# pcbremote.net
KiCad netlist of a schematic drawn in EAGLE
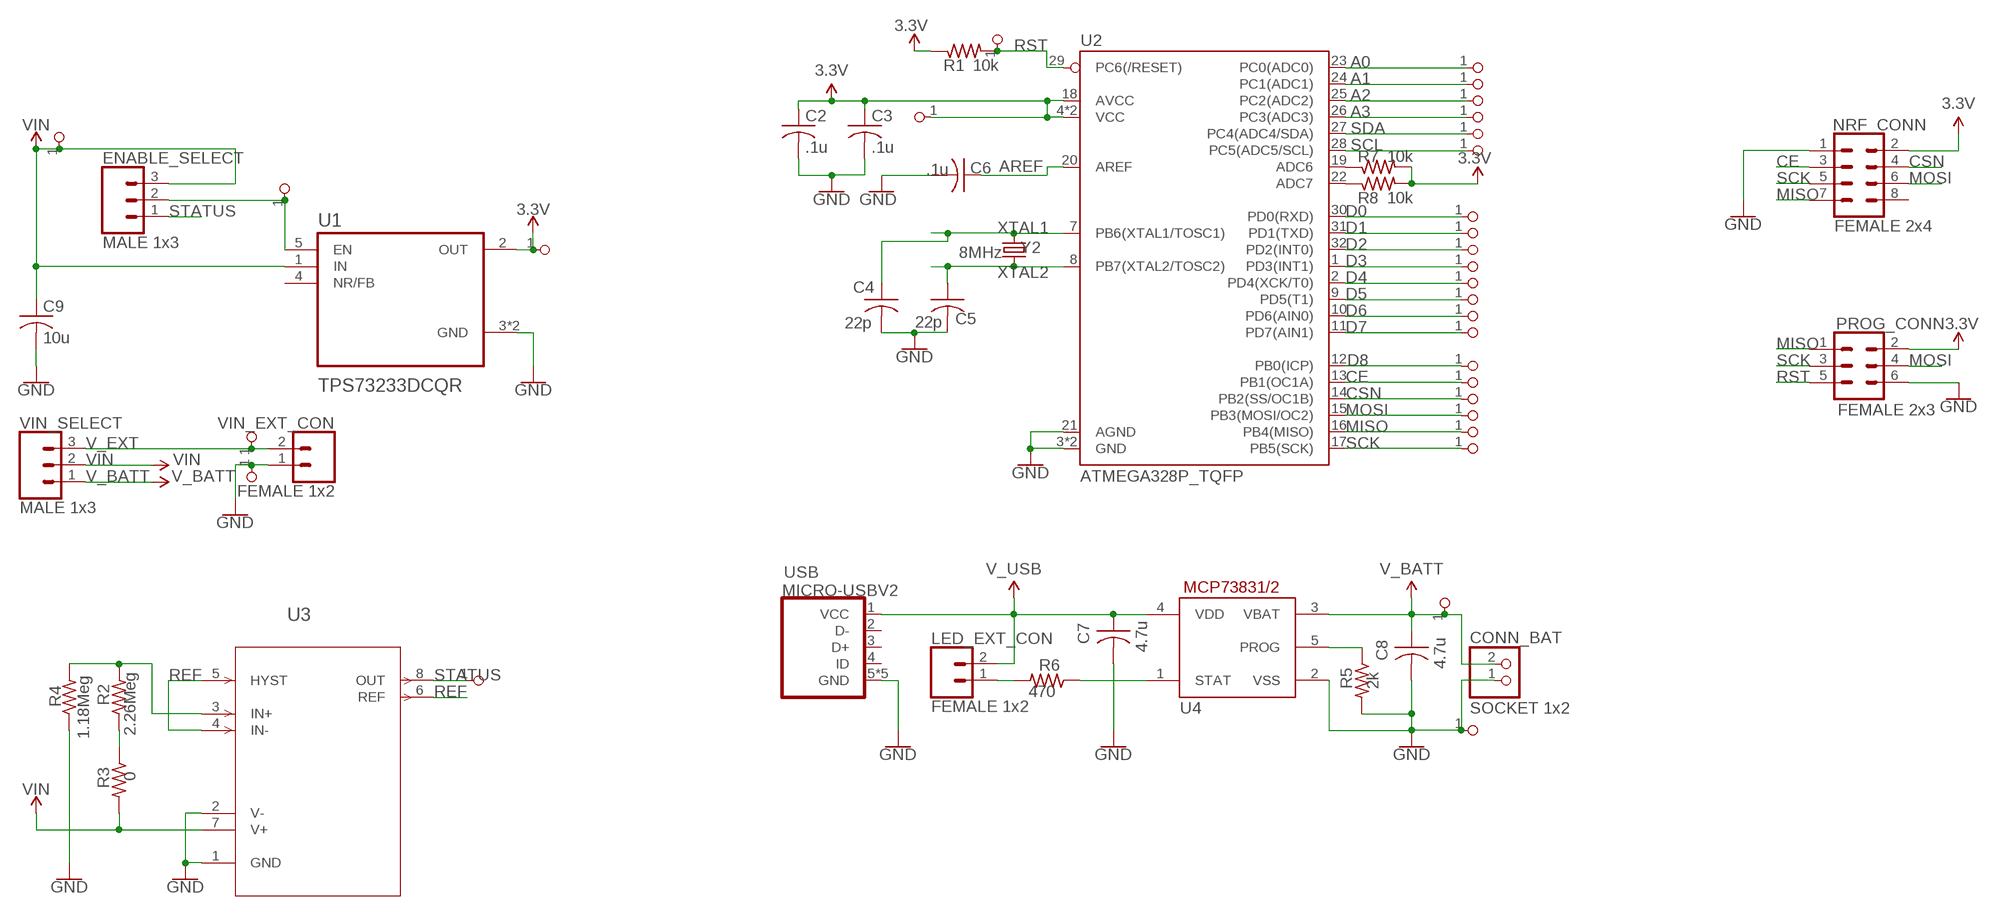
[diagram p0: schematic, sheet 1]

(export (version "E")
  (design (tool "Eeschema 10.0.6"))
  (components
    (comp (ref "3.3V")
      (value "PINHD-1X1")
      (footprint "eagle-import:1X01")
      (libsource (lib "eagle-import") (part "PINHD-1X1"))
    )
    (comp (ref "A0")
      (value "PINHD-1X1")
      (footprint "eagle-import:1X01")
      (libsource (lib "eagle-import") (part "PINHD-1X1"))
    )
    (comp (ref "A1")
      (value "PINHD-1X1")
      (footprint "eagle-import:1X01")
      (libsource (lib "eagle-import") (part "PINHD-1X1"))
    )
    (comp (ref "A2")
      (value "PINHD-1X1")
      (footprint "eagle-import:1X01")
      (libsource (lib "eagle-import") (part "PINHD-1X1"))
    )
    (comp (ref "A3")
      (value "PINHD-1X1")
      (footprint "eagle-import:1X01")
      (libsource (lib "eagle-import") (part "PINHD-1X1"))
    )
    (comp (ref "C2")
      (value ".1u")
      (footprint "eagle-import:C0805")
      (libsource (lib "eagle-import") (part "C-USC0805"))
    )
    (comp (ref "C3")
      (value ".1u")
      (footprint "eagle-import:C0805")
      (libsource (lib "eagle-import") (part "C-USC0805"))
    )
    (comp (ref "C4")
      (value "22p")
      (footprint "eagle-import:C0805")
      (libsource (lib "eagle-import") (part "C-USC0805"))
    )
    (comp (ref "C5")
      (value "22p")
      (footprint "eagle-import:C0805")
      (libsource (lib "eagle-import") (part "C-USC0805"))
    )
    (comp (ref "C6")
      (value ".1u")
      (footprint "eagle-import:C0805")
      (libsource (lib "eagle-import") (part "C-USC0805"))
    )
    (comp (ref "C7")
      (value "4.7u")
      (footprint "eagle-import:C0805")
      (libsource (lib "eagle-import") (part "C-USC0805"))
    )
    (comp (ref "C8")
      (value "4.7u")
      (footprint "eagle-import:C0805")
      (libsource (lib "eagle-import") (part "C-USC0805"))
    )
    (comp (ref "C9")
      (value "10u")
      (footprint "eagle-import:C0805")
      (libsource (lib "eagle-import") (part "C-USC0805"))
    )
    (comp (ref "CE")
      (value "PINHD-1X1")
      (footprint "eagle-import:1X01")
      (libsource (lib "eagle-import") (part "PINHD-1X1"))
    )
    (comp (ref "CONN_BAT")
      (value "SOCKET 1x2")
      (footprint "eagle-import:JST-PH-2-THM")
      (libsource (lib "eagle-import") (part "JST_2PIN-THM"))
    )
    (comp (ref "CSN")
      (value "PINHD-1X1")
      (footprint "eagle-import:1X01")
      (libsource (lib "eagle-import") (part "PINHD-1X1"))
    )
    (comp (ref "D0")
      (value "PINHD-1X1")
      (footprint "eagle-import:1X01")
      (libsource (lib "eagle-import") (part "PINHD-1X1"))
    )
    (comp (ref "D1")
      (value "PINHD-1X1")
      (footprint "eagle-import:1X01")
      (libsource (lib "eagle-import") (part "PINHD-1X1"))
    )
    (comp (ref "D2")
      (value "PINHD-1X1")
      (footprint "eagle-import:1X01")
      (libsource (lib "eagle-import") (part "PINHD-1X1"))
    )
    (comp (ref "D3")
      (value "PINHD-1X1")
      (footprint "eagle-import:1X01")
      (libsource (lib "eagle-import") (part "PINHD-1X1"))
    )
    (comp (ref "D4")
      (value "PINHD-1X1")
      (footprint "eagle-import:1X01")
      (libsource (lib "eagle-import") (part "PINHD-1X1"))
    )
    (comp (ref "D5")
      (value "PINHD-1X1")
      (footprint "eagle-import:1X01")
      (libsource (lib "eagle-import") (part "PINHD-1X1"))
    )
    (comp (ref "D6")
      (value "PINHD-1X1")
      (footprint "eagle-import:1X01")
      (libsource (lib "eagle-import") (part "PINHD-1X1"))
    )
    (comp (ref "D7")
      (value "PINHD-1X1")
      (footprint "eagle-import:1X01")
      (libsource (lib "eagle-import") (part "PINHD-1X1"))
    )
    (comp (ref "D8")
      (value "PINHD-1X1")
      (footprint "eagle-import:1X01")
      (libsource (lib "eagle-import") (part "PINHD-1X1"))
    )
    (comp (ref "EN")
      (value "PINHD-1X1")
      (footprint "eagle-import:1X01")
      (libsource (lib "eagle-import") (part "PINHD-1X1"))
    )
    (comp (ref "ENABLE_SELECT")
      (value "MALE 1x3")
      (footprint "eagle-import:1X03")
      (libsource (lib "eagle-import") (part "CONN_03"))
    )
    (comp (ref "GND")
      (value "PINHD-1X1")
      (footprint "eagle-import:1X01")
      (libsource (lib "eagle-import") (part "PINHD-1X1"))
    )
    (comp (ref "GND7")
      (value "PINHD-1X1")
      (footprint "eagle-import:1X01")
      (libsource (lib "eagle-import") (part "PINHD-1X1"))
    )
    (comp (ref "LED_EXT_CON")
      (value "FEMALE 1x2")
      (footprint "eagle-import:1X02")
      (libsource (lib "eagle-import") (part "CONN_02"))
    )
    (comp (ref "MISO")
      (value "PINHD-1X1")
      (footprint "eagle-import:1X01")
      (libsource (lib "eagle-import") (part "PINHD-1X1"))
    )
    (comp (ref "MOSI")
      (value "PINHD-1X1")
      (footprint "eagle-import:1X01")
      (libsource (lib "eagle-import") (part "PINHD-1X1"))
    )
    (comp (ref "NRF_CONN")
      (value "FEMALE 2x4")
      (footprint "eagle-import:2X4")
      (libsource (lib "eagle-import") (part "CONN_04X2"))
    )
    (comp (ref "PROG_CONN")
      (value "FEMALE 2x3")
      (footprint "eagle-import:2X3")
      (libsource (lib "eagle-import") (part "CONN_03X2FEMALE"))
    )
    (comp (ref "R1")
      (value "10k")
      (footprint "eagle-import:R0805")
      (libsource (lib "eagle-import") (part "R-US_R0805"))
    )
    (comp (ref "R2")
      (value "2.26Meg")
      (footprint "eagle-import:R0805")
      (libsource (lib "eagle-import") (part "R-US_R0805"))
    )
    (comp (ref "R3")
      (value "0")
      (footprint "eagle-import:R0805")
      (libsource (lib "eagle-import") (part "R-US_R0805"))
    )
    (comp (ref "R4")
      (value "1.18Meg")
      (footprint "eagle-import:R0805")
      (libsource (lib "eagle-import") (part "R-US_R0805"))
    )
    (comp (ref "R5")
      (value "2k")
      (footprint "eagle-import:R0805")
      (libsource (lib "eagle-import") (part "R-US_R0805"))
    )
    (comp (ref "R6")
      (value "470")
      (footprint "eagle-import:R0805")
      (libsource (lib "eagle-import") (part "R-US_R0805"))
    )
    (comp (ref "R7")
      (value "10k")
      (footprint "eagle-import:R0805")
      (libsource (lib "eagle-import") (part "R-US_R0805"))
    )
    (comp (ref "R8")
      (value "10k")
      (footprint "eagle-import:R0805")
      (libsource (lib "eagle-import") (part "R-US_R0805"))
    )
    (comp (ref "RESET")
      (value "PINHD-1X1")
      (footprint "eagle-import:1X01")
      (libsource (lib "eagle-import") (part "PINHD-1X1"))
    )
    (comp (ref "SCK")
      (value "PINHD-1X1")
      (footprint "eagle-import:1X01")
      (libsource (lib "eagle-import") (part "PINHD-1X1"))
    )
    (comp (ref "SCL")
      (value "PINHD-1X1")
      (footprint "eagle-import:1X01")
      (libsource (lib "eagle-import") (part "PINHD-1X1"))
    )
    (comp (ref "SDA")
      (value "PINHD-1X1")
      (footprint "eagle-import:1X01")
      (libsource (lib "eagle-import") (part "PINHD-1X1"))
    )
    (comp (ref "STATUS")
      (value "PINHD-1X1")
      (footprint "eagle-import:1X01")
      (libsource (lib "eagle-import") (part "PINHD-1X1"))
    )
    (comp (ref "U1")
      (value "TPS73233DCQR")
      (footprint "eagle-import:SOT127P706X180-6N")
      (fields (field (name "DIGI-KEY_PART_NUMBER") "296-16866-1-ND") (field (name "MF") "Texas Instruments"))
      (libsource (lib "eagle-import") (part "TPS73233DCQR"))
    )
    (comp (ref "U2")
      (value "ATMEGA328P_TQFP")
      (footprint "eagle-import:TQFP32-08")
      (libsource (lib "eagle-import") (part "ATMEGA328P_TQFP"))
    )
    (comp (ref "U3")
      (value "LTC1540CS8PBF")
      (footprint "eagle-import:SO-8_S_LIT")
      (fields (field (name "MANUFACTURER_PART_NUMBER") "ltc1540cs8#pbf"))
      (libsource (lib "eagle-import") (part "LTC1540CS8PBF"))
    )
    (comp (ref "U4")
      (value "MCP73831/OT")
      (footprint "eagle-import:SOT23-5L")
      (libsource (lib "eagle-import") (part "MCP73831/OT"))
    )
    (comp (ref "USB")
      (value "MICRO-USBV2")
      (footprint "eagle-import:MICRO-USB-2")
      (libsource (lib "eagle-import") (part "MICRO-USBV2"))
    )
    (comp (ref "VCC")
      (value "PINHD-1X1")
      (footprint "eagle-import:1X01")
      (libsource (lib "eagle-import") (part "PINHD-1X1"))
    )
    (comp (ref "VIN")
      (value "PINHD-1X1")
      (footprint "eagle-import:1X01")
      (libsource (lib "eagle-import") (part "PINHD-1X1"))
    )
    (comp (ref "VIN_EXT")
      (value "PINHD-1X1")
      (footprint "eagle-import:1X01")
      (libsource (lib "eagle-import") (part "PINHD-1X1"))
    )
    (comp (ref "VIN_EXT_CON")
      (value "FEMALE 1x2")
      (footprint "eagle-import:1X02")
      (libsource (lib "eagle-import") (part "CONN_02"))
    )
    (comp (ref "VIN_SELECT")
      (value "MALE 1x3")
      (footprint "eagle-import:1X03")
      (libsource (lib "eagle-import") (part "CONN_03"))
    )
    (comp (ref "V_BATT")
      (value "PINHD-1X1")
      (footprint "eagle-import:1X01")
      (libsource (lib "eagle-import") (part "PINHD-1X1"))
    )
    (comp (ref "Y2")
      (value "8MHz")
      (footprint "eagle-import:CRYSTAL-SMD-5X3.2-4PAD")
      (libsource (lib "eagle-import") (part "CRYSTAL-8MHZSMD-5X3.2"))
    )
  )
  (nets
    (net (code "1") (name "/A0") (class "Default")
      (node (ref "A0") (pin "1") (pinfunction "1_1") (pintype "passive"))
      (node (ref "U2") (pin "23") (pinfunction "PC0(ADC0)_23") (pintype "bidirectional"))
    )
    (net (code "2") (name "/A1") (class "Default")
      (node (ref "A1") (pin "1") (pinfunction "1_1") (pintype "passive"))
      (node (ref "U2") (pin "24") (pinfunction "PC1(ADC1)_24") (pintype "bidirectional"))
    )
    (net (code "3") (name "/A2") (class "Default")
      (node (ref "A2") (pin "1") (pinfunction "1_1") (pintype "passive"))
      (node (ref "U2") (pin "25") (pinfunction "PC2(ADC2)_25") (pintype "bidirectional"))
    )
    (net (code "4") (name "/A3") (class "Default")
      (node (ref "A3") (pin "1") (pinfunction "1_1") (pintype "passive"))
      (node (ref "U2") (pin "26") (pinfunction "PC3(ADC3)_26") (pintype "bidirectional"))
    )
    (net (code "5") (name "/AREF") (class "Default")
      (node (ref "C6") (pin "1") (pinfunction "1_1") (pintype "passive"))
      (node (ref "U2") (pin "20") (pinfunction "AREF_20") (pintype "bidirectional"))
    )
    (net (code "6") (name "/CE") (class "Default")
      (node (ref "CE") (pin "1") (pinfunction "1_1") (pintype "passive"))
      (node (ref "NRF_CONN") (pin "3") (pinfunction "3_3") (pintype "passive"))
      (node (ref "U2") (pin "13") (pinfunction "PB1(OC1A)_13") (pintype "bidirectional"))
    )
    (net (code "7") (name "/CSN") (class "Default")
      (node (ref "CSN") (pin "1") (pinfunction "1_1") (pintype "passive"))
      (node (ref "NRF_CONN") (pin "4") (pinfunction "4_4") (pintype "passive"))
      (node (ref "U2") (pin "14") (pinfunction "PB2(SS/OC1B)_14") (pintype "bidirectional"))
    )
    (net (code "8") (name "/D0") (class "Default")
      (node (ref "D0") (pin "1") (pinfunction "1_1") (pintype "passive"))
      (node (ref "U2") (pin "30") (pinfunction "PD0(RXD)_30") (pintype "bidirectional"))
    )
    (net (code "9") (name "/D1") (class "Default")
      (node (ref "D1") (pin "1") (pinfunction "1_1") (pintype "passive"))
      (node (ref "U2") (pin "31") (pinfunction "PD1(TXD)_31") (pintype "bidirectional"))
    )
    (net (code "10") (name "/D2") (class "Default")
      (node (ref "D2") (pin "1") (pinfunction "1_1") (pintype "passive"))
      (node (ref "U2") (pin "32") (pinfunction "PD2(INT0)_32") (pintype "bidirectional"))
    )
    (net (code "11") (name "/D3") (class "Default")
      (node (ref "D3") (pin "1") (pinfunction "1_1") (pintype "passive"))
      (node (ref "U2") (pin "1") (pinfunction "PD3(INT1)_1") (pintype "bidirectional"))
    )
    (net (code "12") (name "/D4") (class "Default")
      (node (ref "D4") (pin "1") (pinfunction "1_1") (pintype "passive"))
      (node (ref "U2") (pin "2") (pinfunction "PD4(XCK/T0)_2") (pintype "bidirectional"))
    )
    (net (code "13") (name "/D5") (class "Default")
      (node (ref "D5") (pin "1") (pinfunction "1_1") (pintype "passive"))
      (node (ref "U2") (pin "9") (pinfunction "PD5(T1)_9") (pintype "bidirectional"))
    )
    (net (code "14") (name "/D6") (class "Default")
      (node (ref "D6") (pin "1") (pinfunction "1_1") (pintype "passive"))
      (node (ref "U2") (pin "10") (pinfunction "PD6(AIN0)_10") (pintype "bidirectional"))
    )
    (net (code "15") (name "/D7") (class "Default")
      (node (ref "D7") (pin "1") (pinfunction "1_1") (pintype "passive"))
      (node (ref "U2") (pin "11") (pinfunction "PD7(AIN1)_11") (pintype "bidirectional"))
    )
    (net (code "16") (name "/D8") (class "Default")
      (node (ref "D8") (pin "1") (pinfunction "1_1") (pintype "passive"))
      (node (ref "U2") (pin "12") (pinfunction "PB0(ICP)_12") (pintype "bidirectional"))
    )
    (net (code "17") (name "/MISO") (class "Default")
      (node (ref "MISO") (pin "1") (pinfunction "1_1") (pintype "passive"))
      (node (ref "NRF_CONN") (pin "7") (pinfunction "7_7") (pintype "passive"))
      (node (ref "PROG_CONN") (pin "1") (pinfunction "1_1") (pintype "bidirectional"))
      (node (ref "U2") (pin "16") (pinfunction "PB4(MISO)_16") (pintype "bidirectional"))
    )
    (net (code "18") (name "/MOSI") (class "Default")
      (node (ref "MOSI") (pin "1") (pinfunction "1_1") (pintype "passive"))
      (node (ref "NRF_CONN") (pin "6") (pinfunction "6_6") (pintype "passive"))
      (node (ref "PROG_CONN") (pin "4") (pinfunction "4_4") (pintype "bidirectional"))
      (node (ref "U2") (pin "15") (pinfunction "PB3(MOSI/OC2)_15") (pintype "bidirectional"))
    )
    (net (code "19") (name "/REF") (class "Default")
      (node (ref "U3") (pin "4") (pinfunction "IN-_4") (pintype "input"))
      (node (ref "U3") (pin "5") (pinfunction "HYST_5") (pintype "input"))
      (node (ref "U3") (pin "6") (pinfunction "REF_6") (pintype "output"))
    )
    (net (code "20") (name "/RST") (class "Default")
      (node (ref "PROG_CONN") (pin "5") (pinfunction "5_5") (pintype "bidirectional"))
      (node (ref "R1") (pin "2") (pinfunction "2_2") (pintype "passive"))
      (node (ref "RESET") (pin "1") (pinfunction "1_1") (pintype "passive"))
      (node (ref "U2") (pin "29") (pinfunction "PC6(/RESET)_29") (pintype "bidirectional"))
    )
    (net (code "21") (name "/SCK") (class "Default")
      (node (ref "NRF_CONN") (pin "5") (pinfunction "5_5") (pintype "passive"))
      (node (ref "PROG_CONN") (pin "3") (pinfunction "3_3") (pintype "bidirectional"))
      (node (ref "SCK") (pin "1") (pinfunction "1_1") (pintype "passive"))
      (node (ref "U2") (pin "17") (pinfunction "PB5(SCK)_17") (pintype "bidirectional"))
    )
    (net (code "22") (name "/SCL") (class "Default")
      (node (ref "SCL") (pin "1") (pinfunction "1_1") (pintype "passive"))
      (node (ref "U2") (pin "28") (pinfunction "PC5(ADC5/SCL)_28") (pintype "bidirectional"))
    )
    (net (code "23") (name "/SDA") (class "Default")
      (node (ref "SDA") (pin "1") (pinfunction "1_1") (pintype "passive"))
      (node (ref "U2") (pin "27") (pinfunction "PC4(ADC4/SDA)_27") (pintype "bidirectional"))
    )
    (net (code "24") (name "/STATUS") (class "Default")
      (node (ref "ENABLE_SELECT") (pin "1") (pinfunction "1_1") (pintype "passive"))
      (node (ref "STATUS") (pin "1") (pinfunction "1_1") (pintype "passive"))
      (node (ref "U3") (pin "8") (pinfunction "OUT_8") (pintype "output"))
    )
    (net (code "25") (name "/V_EXT") (class "Default")
      (node (ref "VIN_EXT") (pin "1") (pinfunction "1_1") (pintype "passive"))
      (node (ref "VIN_EXT_CON") (pin "2") (pinfunction "2_2") (pintype "passive"))
      (node (ref "VIN_SELECT") (pin "3") (pinfunction "3_3") (pintype "passive"))
    )
    (net (code "26") (name "/XTAL1") (class "Default")
      (node (ref "C4") (pin "1") (pinfunction "1_1") (pintype "passive"))
      (node (ref "U2") (pin "7") (pinfunction "PB6(XTAL1/TOSC1)_7") (pintype "bidirectional"))
      (node (ref "Y2") (pin "1") (pinfunction "1_1") (pintype "passive"))
    )
    (net (code "27") (name "/XTAL2") (class "Default")
      (node (ref "C5") (pin "1") (pinfunction "1_1") (pintype "passive"))
      (node (ref "U2") (pin "8") (pinfunction "PB7(XTAL2/TOSC2)_8") (pintype "bidirectional"))
      (node (ref "Y2") (pin "3") (pinfunction "2_3") (pintype "passive"))
    )
    (net (code "28") (name "3.3V") (class "Default")
      (node (ref "3.3V") (pin "1") (pinfunction "1_1") (pintype "passive"))
      (node (ref "C2") (pin "1") (pinfunction "1_1") (pintype "passive"))
      (node (ref "C3") (pin "1") (pinfunction "1_1") (pintype "passive"))
      (node (ref "NRF_CONN") (pin "2") (pinfunction "2_2") (pintype "passive"))
      (node (ref "PROG_CONN") (pin "2") (pinfunction "2_2") (pintype "bidirectional"))
      (node (ref "R1") (pin "1") (pinfunction "1_1") (pintype "passive"))
      (node (ref "R7") (pin "2") (pinfunction "2_2") (pintype "passive"))
      (node (ref "R8") (pin "2") (pinfunction "2_2") (pintype "passive"))
      (node (ref "U1") (pin "2") (pinfunction "OUT_2") (pintype "output"))
      (node (ref "U2") (pin "18") (pinfunction "AVCC_18") (pintype "bidirectional"))
      (node (ref "U2") (pin "4") (pinfunction "VCC_4") (pintype "bidirectional"))
      (node (ref "U2") (pin "6") (pinfunction "VCC_6") (pintype "bidirectional"))
      (node (ref "VCC") (pin "1") (pinfunction "1_1") (pintype "passive"))
    )
    (net (code "29") (name "GND") (class "Default")
      (node (ref "C2") (pin "2") (pinfunction "2_2") (pintype "passive"))
      (node (ref "C3") (pin "2") (pinfunction "2_2") (pintype "passive"))
      (node (ref "C4") (pin "2") (pinfunction "2_2") (pintype "passive"))
      (node (ref "C5") (pin "2") (pinfunction "2_2") (pintype "passive"))
      (node (ref "C6") (pin "2") (pinfunction "2_2") (pintype "passive"))
      (node (ref "C7") (pin "2") (pinfunction "2_2") (pintype "passive"))
      (node (ref "C8") (pin "2") (pinfunction "2_2") (pintype "passive"))
      (node (ref "C9") (pin "2") (pinfunction "2_2") (pintype "passive"))
      (node (ref "CONN_BAT") (pin "1") (pinfunction "2_1") (pintype "passive"))
      (node (ref "GND") (pin "1") (pinfunction "1_1") (pintype "passive"))
      (node (ref "GND7") (pin "1") (pinfunction "1_1") (pintype "passive"))
      (node (ref "NRF_CONN") (pin "1") (pinfunction "1_1") (pintype "passive"))
      (node (ref "PROG_CONN") (pin "6") (pinfunction "6_6") (pintype "bidirectional"))
      (node (ref "R4") (pin "1") (pinfunction "1_1") (pintype "passive"))
      (node (ref "R5") (pin "2") (pinfunction "2_2") (pintype "passive"))
      (node (ref "U1") (pin "3") (pinfunction "GND_3") (pintype "power_in"))
      (node (ref "U1") (pin "6") (pinfunction "GND_6") (pintype "power_in"))
      (node (ref "U2") (pin "21") (pinfunction "AGND_21") (pintype "bidirectional"))
      (node (ref "U2") (pin "3") (pinfunction "GND_3") (pintype "bidirectional"))
      (node (ref "U2") (pin "5") (pinfunction "GND_5") (pintype "bidirectional"))
      (node (ref "U3") (pin "1") (pinfunction "GND_1") (pintype "power_in"))
      (node (ref "U3") (pin "2") (pinfunction "V-_2") (pintype "power_in"))
      (node (ref "U4") (pin "2") (pinfunction "VSS_2") (pintype "power_in"))
      (node (ref "USB") (pin "5") (pinfunction "GND_5") (pintype "power_in"))
      (node (ref "USB") (pin "P$1") (pinfunction "GND_P$1") (pintype "power_in"))
      (node (ref "USB") (pin "P$2") (pinfunction "GND_P$2") (pintype "power_in"))
      (node (ref "USB") (pin "P$3") (pinfunction "GND_P$3") (pintype "power_in"))
      (node (ref "USB") (pin "P$4") (pinfunction "GND_P$4") (pintype "power_in"))
      (node (ref "VIN_EXT_CON") (pin "1") (pinfunction "1_1") (pintype "passive"))
    )
    (net (code "30") (name "Net-(LED_EXT_CON-Pad1)") (class "Default")
      (node (ref "LED_EXT_CON") (pin "1") (pinfunction "1_1") (pintype "passive"))
      (node (ref "R6") (pin "2") (pinfunction "2_2") (pintype "passive"))
    )
    (net (code "31") (name "Net-(R2-Pad1)") (class "Default")
      (node (ref "R2") (pin "1") (pinfunction "1_1") (pintype "passive"))
      (node (ref "R3") (pin "1") (pinfunction "1_1") (pintype "passive"))
    )
    (net (code "32") (name "Net-(U1-EN)") (class "Default")
      (node (ref "EN") (pin "1") (pinfunction "1_1") (pintype "passive"))
      (node (ref "ENABLE_SELECT") (pin "2") (pinfunction "2_2") (pintype "passive"))
      (node (ref "U1") (pin "5") (pinfunction "EN_5") (pintype "input"))
    )
    (net (code "33") (name "Net-(U2-ADC6)") (class "Default")
      (node (ref "R7") (pin "1") (pinfunction "1_1") (pintype "passive"))
      (node (ref "U2") (pin "19") (pinfunction "ADC6_19") (pintype "bidirectional"))
    )
    (net (code "34") (name "Net-(U2-ADC7)") (class "Default")
      (node (ref "R8") (pin "1") (pinfunction "1_1") (pintype "passive"))
      (node (ref "U2") (pin "22") (pinfunction "ADC7_22") (pintype "bidirectional"))
    )
    (net (code "35") (name "Net-(U3-IN+)") (class "Default")
      (node (ref "R2") (pin "2") (pinfunction "2_2") (pintype "passive"))
      (node (ref "R4") (pin "2") (pinfunction "2_2") (pintype "passive"))
      (node (ref "U3") (pin "3") (pinfunction "IN+_3") (pintype "input"))
    )
    (net (code "36") (name "Net-(U4-PROG)") (class "Default")
      (node (ref "R5") (pin "1") (pinfunction "1_1") (pintype "passive"))
      (node (ref "U4") (pin "5") (pinfunction "PROG_5") (pintype "input"))
    )
    (net (code "37") (name "Net-(U4-STAT)") (class "Default")
      (node (ref "R6") (pin "1") (pinfunction "1_1") (pintype "passive"))
      (node (ref "U4") (pin "1") (pinfunction "STAT_1") (pintype "output"))
    )
    (net (code "38") (name "VIN") (class "Default")
      (node (ref "C9") (pin "1") (pinfunction "1_1") (pintype "passive"))
      (node (ref "ENABLE_SELECT") (pin "3") (pinfunction "3_3") (pintype "passive"))
      (node (ref "R3") (pin "2") (pinfunction "2_2") (pintype "passive"))
      (node (ref "U1") (pin "1") (pinfunction "IN_1") (pintype "input"))
      (node (ref "U3") (pin "7") (pinfunction "V+_7") (pintype "power_in"))
      (node (ref "VIN") (pin "1") (pinfunction "1_1") (pintype "passive"))
      (node (ref "VIN_SELECT") (pin "2") (pinfunction "2_2") (pintype "passive"))
    )
    (net (code "39") (name "V_BATT") (class "Default")
      (node (ref "C8") (pin "1") (pinfunction "1_1") (pintype "passive"))
      (node (ref "CONN_BAT") (pin "2") (pinfunction "1_2") (pintype "passive"))
      (node (ref "U4") (pin "3") (pinfunction "VBAT_3") (pintype "bidirectional"))
      (node (ref "VIN_SELECT") (pin "1") (pinfunction "1_1") (pintype "passive"))
      (node (ref "V_BATT") (pin "1") (pinfunction "1_1") (pintype "passive"))
    )
    (net (code "40") (name "V_USB") (class "Default")
      (node (ref "C7") (pin "1") (pinfunction "1_1") (pintype "passive"))
      (node (ref "LED_EXT_CON") (pin "2") (pinfunction "2_2") (pintype "passive"))
      (node (ref "U4") (pin "4") (pinfunction "VDD_4") (pintype "power_in"))
      (node (ref "USB") (pin "1") (pinfunction "VCC_1") (pintype "power_in"))
    )
    (net (code "41") (name "unconnected-(NRF_CONN-Pad8)") (class "Default")
      (node (ref "NRF_CONN") (pin "8") (pinfunction "8_8") (pintype "passive"))
    )
    (net (code "42") (name "unconnected-(U1-NR{slash}FB-Pad4)") (class "Default")
      (node (ref "U1") (pin "4") (pinfunction "NR/FB_4") (pintype "input"))
    )
    (net (code "43") (name "unconnected-(USB-D+-Pad3)") (class "Default")
      (node (ref "USB") (pin "3") (pinfunction "D+_3") (pintype "bidirectional"))
    )
    (net (code "44") (name "unconnected-(USB-D--Pad2)") (class "Default")
      (node (ref "USB") (pin "2") (pinfunction "D-_2") (pintype "bidirectional"))
    )
    (net (code "45") (name "unconnected-(USB-ID-Pad4)") (class "Default")
      (node (ref "USB") (pin "4") (pinfunction "ID_4") (pintype "bidirectional"))
    )
  )
)
